# DCDC.net
KiCad netlist of a schematic drawn in Altium Designer
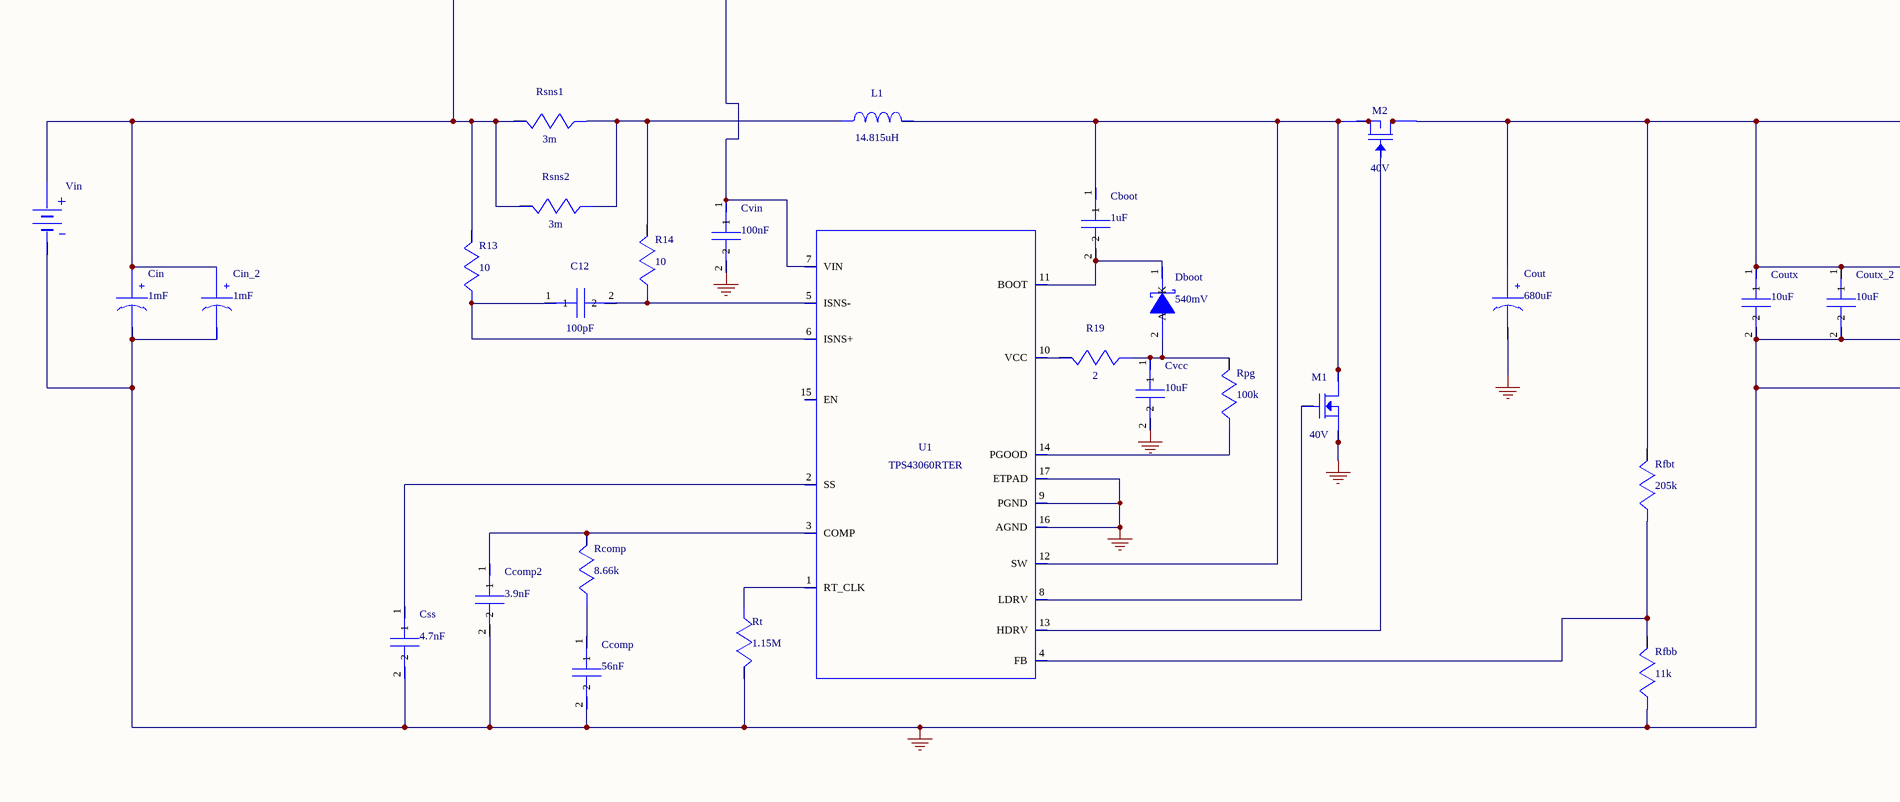
[diagram p0: DCDC.SchDoc, left]
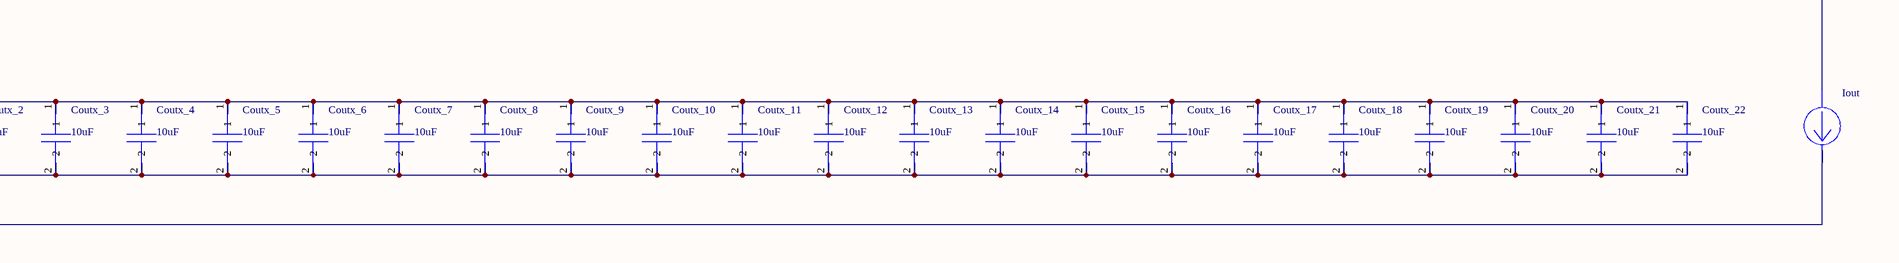
[diagram p1: DCDC.SchDoc, right]

(export (version "E")
  (design (tool "Eeschema 10.0.6"))
  (components
    (comp (ref "C12")
      (value "100pF")
      (description "06035A101JAT2A")
      (libsource (lib "TI WEBENCH") (part "C12"))
    )
    (comp (ref "Cboot")
      (value "1uF")
      (description "GRM188R61C105KA9")
      (fields (field (name "MANUFACTURER PART NUMBER") "GRM188R61C105KA93D"))
      (libsource (lib "TI WEBENCH") (part "Cboot"))
    )
    (comp (ref "Ccomp")
      (value "56nF")
      (description "GRM155R61A563KA0")
      (fields (field (name "MANUFACTURER PART NUMBER") "GRM155R61A563KA01D"))
      (libsource (lib "TI WEBENCH") (part "Ccomp"))
    )
    (comp (ref "Ccomp2")
      (value "3.9nF")
      (description "CC0805KRX7R9BB39")
      (fields (field (name "MANUFACTURER PART NUMBER") "CC0805KRX7R9BB392"))
      (libsource (lib "TI WEBENCH") (part "Ccomp2"))
    )
    (comp (ref "Cin") (value "1mF") (description "16SVPF1000M") (libsource (lib "TI WEBENCH") (part "Cin")))
    (comp (ref "Cin_2")
      (value "1mF")
      (description "16SVPF1000M")
      (libsource (lib "TI WEBENCH") (part "Cin_2"))
    )
    (comp (ref "Cout")
      (value "680uF")
      (description "EEV-FK1H681M")
      (libsource (lib "TI WEBENCH") (part "Cout"))
    )
    (comp (ref "Coutx")
      (value "10uF")
      (description "C3216JB1H106K")
      (libsource (lib "TI WEBENCH") (part "Coutx"))
    )
    (comp (ref "Coutx_2")
      (value "10uF")
      (description "C3216JB1H106K")
      (libsource (lib "TI WEBENCH") (part "Coutx_2"))
    )
    (comp (ref "Coutx_3")
      (value "10uF")
      (description "C3216JB1H106K")
      (libsource (lib "TI WEBENCH") (part "Coutx_3"))
    )
    (comp (ref "Coutx_4")
      (value "10uF")
      (description "C3216JB1H106K")
      (libsource (lib "TI WEBENCH") (part "Coutx_4"))
    )
    (comp (ref "Coutx_5")
      (value "10uF")
      (description "C3216JB1H106K")
      (libsource (lib "TI WEBENCH") (part "Coutx_5"))
    )
    (comp (ref "Coutx_6")
      (value "10uF")
      (description "C3216JB1H106K")
      (libsource (lib "TI WEBENCH") (part "Coutx_6"))
    )
    (comp (ref "Coutx_7")
      (value "10uF")
      (description "C3216JB1H106K")
      (libsource (lib "TI WEBENCH") (part "Coutx_7"))
    )
    (comp (ref "Coutx_8")
      (value "10uF")
      (description "C3216JB1H106K")
      (libsource (lib "TI WEBENCH") (part "Coutx_8"))
    )
    (comp (ref "Coutx_9")
      (value "10uF")
      (description "C3216JB1H106K")
      (libsource (lib "TI WEBENCH") (part "Coutx_9"))
    )
    (comp (ref "Coutx_10")
      (value "10uF")
      (description "C3216JB1H106K")
      (libsource (lib "TI WEBENCH") (part "Coutx_10"))
    )
    (comp (ref "Coutx_11")
      (value "10uF")
      (description "C3216JB1H106K")
      (libsource (lib "TI WEBENCH") (part "Coutx_11"))
    )
    (comp (ref "Coutx_12")
      (value "10uF")
      (description "C3216JB1H106K")
      (libsource (lib "TI WEBENCH") (part "Coutx_12"))
    )
    (comp (ref "Coutx_13")
      (value "10uF")
      (description "C3216JB1H106K")
      (libsource (lib "TI WEBENCH") (part "Coutx_13"))
    )
    (comp (ref "Coutx_14")
      (value "10uF")
      (description "C3216JB1H106K")
      (libsource (lib "TI WEBENCH") (part "Coutx_14"))
    )
    (comp (ref "Coutx_15")
      (value "10uF")
      (description "C3216JB1H106K")
      (libsource (lib "TI WEBENCH") (part "Coutx_15"))
    )
    (comp (ref "Coutx_16")
      (value "10uF")
      (description "C3216JB1H106K")
      (libsource (lib "TI WEBENCH") (part "Coutx_16"))
    )
    (comp (ref "Coutx_17")
      (value "10uF")
      (description "C3216JB1H106K")
      (libsource (lib "TI WEBENCH") (part "Coutx_17"))
    )
    (comp (ref "Coutx_18")
      (value "10uF")
      (description "C3216JB1H106K")
      (libsource (lib "TI WEBENCH") (part "Coutx_18"))
    )
    (comp (ref "Coutx_19")
      (value "10uF")
      (description "C3216JB1H106K")
      (libsource (lib "TI WEBENCH") (part "Coutx_19"))
    )
    (comp (ref "Coutx_20")
      (value "10uF")
      (description "C3216JB1H106K")
      (libsource (lib "TI WEBENCH") (part "Coutx_20"))
    )
    (comp (ref "Coutx_21")
      (value "10uF")
      (description "C3216JB1H106K")
      (libsource (lib "TI WEBENCH") (part "Coutx_21"))
    )
    (comp (ref "Coutx_22")
      (value "10uF")
      (description "C3216JB1H106K")
      (libsource (lib "TI WEBENCH") (part "Coutx_22"))
    )
    (comp (ref "Css")
      (value "4.7nF")
      (description "GRM188R71E472KA0")
      (fields (field (name "MANUFACTURER PART NUMBER") "GRM188R71E472KA01D"))
      (libsource (lib "TI WEBENCH") (part "Css"))
    )
    (comp (ref "Cvcc")
      (value "10uF")
      (description "GRM188R61C106MA7")
      (fields (field (name "MANUFACTURER PART NUMBER") "GRM188R61C106MA73D"))
      (libsource (lib "TI WEBENCH") (part "Cvcc"))
    )
    (comp (ref "Cvin")
      (value "100nF")
      (description "08053C104KAT2A")
      (libsource (lib "TI WEBENCH") (part "Cvin"))
    )
    (comp (ref "Dboot")
      (value "540mV")
      (description "XBS104S13R-G")
      (libsource (lib "TI WEBENCH") (part "Dboot"))
    )
    (comp (ref "Iout") (value "WB_CURRENT_LOAD") (libsource (lib "TI WEBENCH") (part "Iout")))
    (comp (ref "L1")
      (value "14.815uH")
      (description "CUSTOM1")
      (fields (field (name "MANUFACTURER PART NUMBER") "GENERIC_INDUCTOR"))
      (libsource (lib "TI WEBENCH") (part "L1"))
    )
    (comp (ref "M1") (value "40V") (description "FDMS8460") (libsource (lib "TI WEBENCH") (part "M1")))
    (comp (ref "M2") (value "40V") (description "CSD18509Q5B") (libsource (lib "TI WEBENCH") (part "M2")))
    (comp (ref "R13")
      (value "10")
      (description "CRCW040210R0FKED")
      (libsource (lib "TI WEBENCH") (part "R13"))
    )
    (comp (ref "R14")
      (value "10")
      (description "CRCW040210R0FKED")
      (libsource (lib "TI WEBENCH") (part "R14"))
    )
    (comp (ref "R19")
      (value "2")
      (description "CRCW04022R00FKED")
      (libsource (lib "TI WEBENCH") (part "R19"))
    )
    (comp (ref "Rcomp")
      (value "8.66k")
      (description "CRCW04028K66FKED")
      (libsource (lib "TI WEBENCH") (part "Rcomp"))
    )
    (comp (ref "Rfbb")
      (value "11k")
      (description "CRCW040211K0FKED")
      (libsource (lib "TI WEBENCH") (part "Rfbb"))
    )
    (comp (ref "Rfbt")
      (value "205k")
      (description "CRCW0402205KFKED")
      (libsource (lib "TI WEBENCH") (part "Rfbt"))
    )
    (comp (ref "Rpg")
      (value "100k")
      (description "CRCW0402100KFKED")
      (libsource (lib "TI WEBENCH") (part "Rpg"))
    )
    (comp (ref "Rsns1")
      (value "3m")
      (description "WSR33L000FEA")
      (libsource (lib "TI WEBENCH") (part "Rsns1"))
    )
    (comp (ref "Rsns2")
      (value "3m")
      (description "WSR33L000FEA")
      (libsource (lib "TI WEBENCH") (part "Rsns2"))
    )
    (comp (ref "Rt")
      (value "1.15M")
      (description "CRCW04021M15FKED")
      (libsource (lib "TI WEBENCH") (part "Rt"))
    )
    (comp (ref "U1")
      (value "TPS43060RTER")
      (fields (field (name "PACKAGEREFERENCE") "TPS43060RTER"))
      (libsource (lib "TI WEBENCH") (part "U1"))
    )
    (comp (ref "Vin") (value "WB_BATTERY") (libsource (lib "TI WEBENCH") (part "Vin")))
  )
  (nets
    (net (code "1") (name "0") (class "Default")
      (node (ref "Ccomp") (pin "2") (pinfunction "2_2") (pintype "passive"))
      (node (ref "Ccomp2") (pin "2") (pinfunction "2_2") (pintype "passive"))
      (node (ref "Cin") (pin "2") (pinfunction "-_2") (pintype "passive"))
      (node (ref "Cin_2") (pin "2") (pinfunction "-_2") (pintype "passive"))
      (node (ref "Cout") (pin "2") (pinfunction "-_2") (pintype "passive"))
      (node (ref "Coutx") (pin "2") (pinfunction "2_2") (pintype "passive"))
      (node (ref "Coutx_10") (pin "2") (pinfunction "2_2") (pintype "passive"))
      (node (ref "Coutx_11") (pin "2") (pinfunction "2_2") (pintype "passive"))
      (node (ref "Coutx_12") (pin "2") (pinfunction "2_2") (pintype "passive"))
      (node (ref "Coutx_13") (pin "2") (pinfunction "2_2") (pintype "passive"))
      (node (ref "Coutx_14") (pin "2") (pinfunction "2_2") (pintype "passive"))
      (node (ref "Coutx_15") (pin "2") (pinfunction "2_2") (pintype "passive"))
      (node (ref "Coutx_16") (pin "2") (pinfunction "2_2") (pintype "passive"))
      (node (ref "Coutx_17") (pin "2") (pinfunction "2_2") (pintype "passive"))
      (node (ref "Coutx_18") (pin "2") (pinfunction "2_2") (pintype "passive"))
      (node (ref "Coutx_19") (pin "2") (pinfunction "2_2") (pintype "passive"))
      (node (ref "Coutx_2") (pin "2") (pinfunction "2_2") (pintype "passive"))
      (node (ref "Coutx_20") (pin "2") (pinfunction "2_2") (pintype "passive"))
      (node (ref "Coutx_21") (pin "2") (pinfunction "2_2") (pintype "passive"))
      (node (ref "Coutx_22") (pin "2") (pinfunction "2_2") (pintype "passive"))
      (node (ref "Coutx_3") (pin "2") (pinfunction "2_2") (pintype "passive"))
      (node (ref "Coutx_4") (pin "2") (pinfunction "2_2") (pintype "passive"))
      (node (ref "Coutx_5") (pin "2") (pinfunction "2_2") (pintype "passive"))
      (node (ref "Coutx_6") (pin "2") (pinfunction "2_2") (pintype "passive"))
      (node (ref "Coutx_7") (pin "2") (pinfunction "2_2") (pintype "passive"))
      (node (ref "Coutx_8") (pin "2") (pinfunction "2_2") (pintype "passive"))
      (node (ref "Coutx_9") (pin "2") (pinfunction "2_2") (pintype "passive"))
      (node (ref "Css") (pin "2") (pinfunction "2_2") (pintype "passive"))
      (node (ref "Cvcc") (pin "2") (pinfunction "2_2") (pintype "passive"))
      (node (ref "Cvin") (pin "2") (pinfunction "2_2") (pintype "passive"))
      (node (ref "Iout") (pin "2") (pinfunction "-_2") (pintype "passive"))
      (node (ref "M1") (pin "1") (pinfunction "Source_1") (pintype "passive"))
      (node (ref "M1") (pin "2") (pinfunction "Source_2") (pintype "passive"))
      (node (ref "M1") (pin "3") (pinfunction "Source_3") (pintype "passive"))
      (node (ref "Rfbb") (pin "2") (pinfunction "2_2") (pintype "passive"))
      (node (ref "Rt") (pin "1") (pinfunction "1_1") (pintype "passive"))
      (node (ref "U1") (pin "16") (pinfunction "AGND_16") (pintype "passive"))
      (node (ref "U1") (pin "17") (pinfunction "ETPAD_17") (pintype "passive"))
      (node (ref "U1") (pin "9") (pinfunction "PGND_9") (pintype "passive"))
      (node (ref "Vin") (pin "2") (pinfunction "-_2") (pintype "passive"))
    )
    (net (code "2") (name "Net-(Ccomp-Pad1)") (class "Default")
      (node (ref "Ccomp") (pin "1") (pinfunction "1_1") (pintype "passive"))
      (node (ref "Rcomp") (pin "2") (pinfunction "2_2") (pintype "passive"))
    )
    (net (code "3") (name "Net-(Cin-+)") (class "Default")
      (node (ref "Cin") (pin "1") (pinfunction "+_1") (pintype "passive"))
      (node (ref "Cin_2") (pin "1") (pinfunction "+_1") (pintype "passive"))
      (node (ref "Cvin") (pin "1") (pinfunction "1_1") (pintype "passive"))
      (node (ref "R13") (pin "1") (pinfunction "1_1") (pintype "passive"))
      (node (ref "Rsns1") (pin "1") (pinfunction "1_1") (pintype "passive"))
      (node (ref "Rsns2") (pin "1") (pinfunction "1_1") (pintype "passive"))
      (node (ref "U1") (pin "7") (pinfunction "VIN_7") (pintype "passive"))
      (node (ref "Vin") (pin "1") (pinfunction "+_1") (pintype "passive"))
    )
    (net (code "4") (name "Net-(Cout-+)") (class "Default")
      (node (ref "Cout") (pin "1") (pinfunction "+_1") (pintype "passive"))
      (node (ref "Coutx") (pin "1") (pinfunction "1_1") (pintype "passive"))
      (node (ref "Coutx_10") (pin "1") (pinfunction "1_1") (pintype "passive"))
      (node (ref "Coutx_11") (pin "1") (pinfunction "1_1") (pintype "passive"))
      (node (ref "Coutx_12") (pin "1") (pinfunction "1_1") (pintype "passive"))
      (node (ref "Coutx_13") (pin "1") (pinfunction "1_1") (pintype "passive"))
      (node (ref "Coutx_14") (pin "1") (pinfunction "1_1") (pintype "passive"))
      (node (ref "Coutx_15") (pin "1") (pinfunction "1_1") (pintype "passive"))
      (node (ref "Coutx_16") (pin "1") (pinfunction "1_1") (pintype "passive"))
      (node (ref "Coutx_17") (pin "1") (pinfunction "1_1") (pintype "passive"))
      (node (ref "Coutx_18") (pin "1") (pinfunction "1_1") (pintype "passive"))
      (node (ref "Coutx_19") (pin "1") (pinfunction "1_1") (pintype "passive"))
      (node (ref "Coutx_2") (pin "1") (pinfunction "1_1") (pintype "passive"))
      (node (ref "Coutx_20") (pin "1") (pinfunction "1_1") (pintype "passive"))
      (node (ref "Coutx_21") (pin "1") (pinfunction "1_1") (pintype "passive"))
      (node (ref "Coutx_22") (pin "1") (pinfunction "1_1") (pintype "passive"))
      (node (ref "Coutx_3") (pin "1") (pinfunction "1_1") (pintype "passive"))
      (node (ref "Coutx_4") (pin "1") (pinfunction "1_1") (pintype "passive"))
      (node (ref "Coutx_5") (pin "1") (pinfunction "1_1") (pintype "passive"))
      (node (ref "Coutx_6") (pin "1") (pinfunction "1_1") (pintype "passive"))
      (node (ref "Coutx_7") (pin "1") (pinfunction "1_1") (pintype "passive"))
      (node (ref "Coutx_8") (pin "1") (pinfunction "1_1") (pintype "passive"))
      (node (ref "Coutx_9") (pin "1") (pinfunction "1_1") (pintype "passive"))
      (node (ref "Iout") (pin "1") (pinfunction "+_1") (pintype "passive"))
      (node (ref "Rfbt") (pin "1") (pinfunction "1_1") (pintype "passive"))
    )
    (net (code "5") (name "Net-(Dboot-A)") (class "Default")
      (node (ref "Cvcc") (pin "1") (pinfunction "1_1") (pintype "passive"))
      (node (ref "Dboot") (pin "2") (pinfunction "A_2") (pintype "passive"))
      (node (ref "R19") (pin "2") (pinfunction "2_2") (pintype "passive"))
      (node (ref "Rpg") (pin "1") (pinfunction "1_1") (pintype "passive"))
    )
    (net (code "6") (name "Net-(Dboot-K)") (class "Default")
      (node (ref "Cboot") (pin "2") (pinfunction "2_2") (pintype "passive"))
      (node (ref "Dboot") (pin "1") (pinfunction "K_1") (pintype "passive"))
      (node (ref "U1") (pin "11") (pinfunction "BOOT_11") (pintype "passive"))
    )
    (net (code "7") (name "Net-(L1-Pad2)") (class "Default")
      (node (ref "L1") (pin "2") (pinfunction "2_2") (pintype "passive"))
      (node (ref "R14") (pin "1") (pinfunction "1_1") (pintype "passive"))
      (node (ref "Rsns1") (pin "2") (pinfunction "2_2") (pintype "passive"))
      (node (ref "Rsns2") (pin "2") (pinfunction "2_2") (pintype "passive"))
    )
    (net (code "8") (name "Net-(M1-Gate)") (class "Default")
      (node (ref "M1") (pin "4") (pinfunction "Gate_4") (pintype "passive"))
      (node (ref "U1") (pin "8") (pinfunction "LDRV_8") (pintype "passive"))
    )
    (net (code "9") (name "Net-(M2-Drain-Pad5)") (class "Default")
      (node (ref "M2") (pin "5") (pinfunction "Drain_5") (pintype "passive"))
      (node (ref "M2") (pin "6") (pinfunction "Drain_6") (pintype "passive"))
      (node (ref "M2") (pin "7") (pinfunction "Drain_7") (pintype "passive"))
      (node (ref "M2") (pin "8") (pinfunction "Drain_8") (pintype "passive"))
      (node (ref "M2") (pin "9") (pinfunction "Drain_9") (pintype "passive"))
    )
    (net (code "10") (name "Net-(M2-Gate)") (class "Default")
      (node (ref "M2") (pin "4") (pinfunction "Gate_4") (pintype "passive"))
      (node (ref "U1") (pin "13") (pinfunction "HDRV_13") (pintype "passive"))
    )
    (net (code "11") (name "Net-(M2-Source-Pad1)") (class "Default")
      (node (ref "M2") (pin "1") (pinfunction "Source_1") (pintype "passive"))
      (node (ref "M2") (pin "2") (pinfunction "Source_2") (pintype "passive"))
      (node (ref "M2") (pin "3") (pinfunction "Source_3") (pintype "passive"))
    )
    (net (code "12") (name "Net-(U1-COMP)") (class "Default")
      (node (ref "Ccomp2") (pin "1") (pinfunction "1_1") (pintype "passive"))
      (node (ref "Rcomp") (pin "1") (pinfunction "1_1") (pintype "passive"))
      (node (ref "U1") (pin "3") (pinfunction "COMP_3") (pintype "passive"))
    )
    (net (code "13") (name "Net-(U1-FB)") (class "Default")
      (node (ref "Rfbb") (pin "1") (pinfunction "1_1") (pintype "passive"))
      (node (ref "Rfbt") (pin "2") (pinfunction "2_2") (pintype "passive"))
      (node (ref "U1") (pin "4") (pinfunction "FB_4") (pintype "passive"))
    )
    (net (code "14") (name "Net-(U1-ISNS+)") (class "Default")
      (node (ref "C12") (pin "1") (pinfunction "1_1") (pintype "passive"))
      (node (ref "R13") (pin "2") (pinfunction "2_2") (pintype "passive"))
      (node (ref "U1") (pin "6") (pinfunction "ISNS+_6") (pintype "passive"))
    )
    (net (code "15") (name "Net-(U1-ISNS-)") (class "Default")
      (node (ref "C12") (pin "2") (pinfunction "2_2") (pintype "passive"))
      (node (ref "R14") (pin "2") (pinfunction "2_2") (pintype "passive"))
      (node (ref "U1") (pin "5") (pinfunction "ISNS-_5") (pintype "passive"))
    )
    (net (code "16") (name "Net-(U1-PGOOD)") (class "Default")
      (node (ref "Rpg") (pin "2") (pinfunction "2_2") (pintype "passive"))
      (node (ref "U1") (pin "14") (pinfunction "PGOOD_14") (pintype "passive"))
    )
    (net (code "17") (name "Net-(U1-RT_CLK)") (class "Default")
      (node (ref "Rt") (pin "2") (pinfunction "2_2") (pintype "passive"))
      (node (ref "U1") (pin "1") (pinfunction "RT_CLK_1") (pintype "passive"))
    )
    (net (code "18") (name "Net-(U1-SS)") (class "Default")
      (node (ref "Css") (pin "1") (pinfunction "1_1") (pintype "passive"))
      (node (ref "U1") (pin "2") (pinfunction "SS_2") (pintype "passive"))
    )
    (net (code "19") (name "Net-(U1-SW)") (class "Default")
      (node (ref "Cboot") (pin "1") (pinfunction "1_1") (pintype "passive"))
      (node (ref "L1") (pin "1") (pinfunction "1_1") (pintype "passive"))
      (node (ref "M1") (pin "5") (pinfunction "Drain_5") (pintype "passive"))
      (node (ref "M1") (pin "6") (pinfunction "Drain_6") (pintype "passive"))
      (node (ref "M1") (pin "7") (pinfunction "Drain_7") (pintype "passive"))
      (node (ref "M1") (pin "8") (pinfunction "Drain_8") (pintype "passive"))
      (node (ref "U1") (pin "12") (pinfunction "SW_12") (pintype "passive"))
    )
    (net (code "20") (name "Net-(U1-VCC)") (class "Default")
      (node (ref "R19") (pin "1") (pinfunction "1_1") (pintype "passive"))
      (node (ref "U1") (pin "10") (pinfunction "VCC_10") (pintype "passive"))
    )
    (net (code "21") (name "unconnected-(U1-EN-Pad15)") (class "Default")
      (node (ref "U1") (pin "15") (pinfunction "EN_15") (pintype "passive"))
    )
  )
)
